# 1_Power.net
KiCad netlist of a schematic drawn in Altium Designer
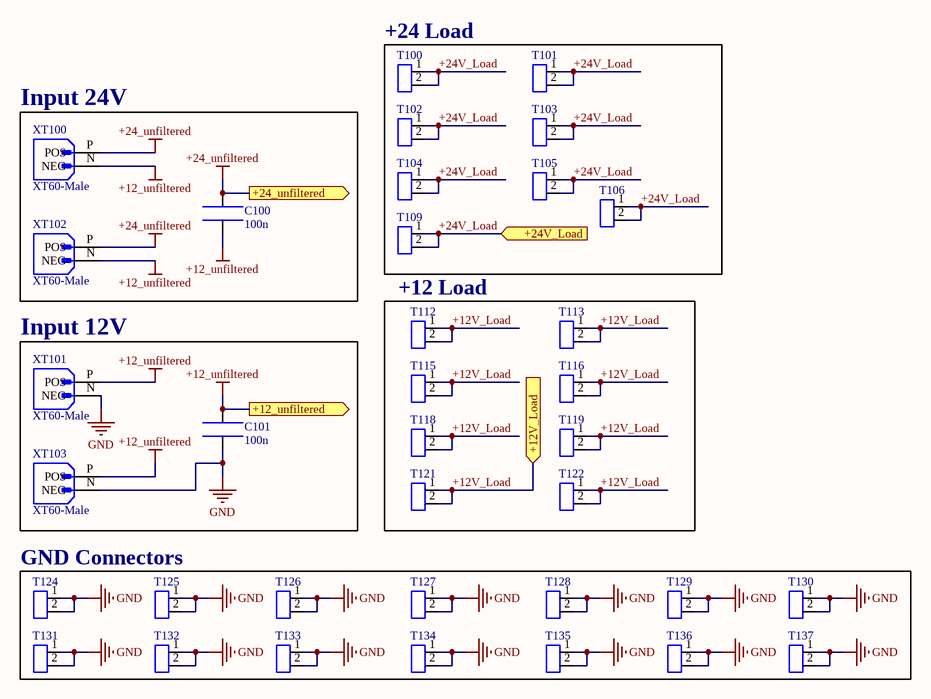
[diagram p0: 1_Power.SchDoc]

(export (version "E")
  (design (tool "Eeschema 10.0.6"))
  (components
    (comp (ref "C100") (value "100n") (footprint "C0805") (libsource (lib "MIA_LIBRARY") (part "C0805")))
    (comp (ref "C101") (value "100n") (footprint "C0805") (libsource (lib "MIA_LIBRARY") (part "C0805")))
    (comp (ref "T100")
      (value "Terminal pin 6.3mm")
      (footprint "Terminal pin 6.3mm")
      (libsource (lib "MIA_LIBRARY") (part "Terminal pin 6.3mm"))
    )
    (comp (ref "T101")
      (value "Terminal pin 6.3mm")
      (footprint "Terminal pin 6.3mm")
      (libsource (lib "MIA_LIBRARY") (part "Terminal pin 6.3mm"))
    )
    (comp (ref "T102")
      (value "Terminal pin 6.3mm")
      (footprint "Terminal pin 6.3mm")
      (libsource (lib "MIA_LIBRARY") (part "Terminal pin 6.3mm"))
    )
    (comp (ref "T103")
      (value "Terminal pin 6.3mm")
      (footprint "Terminal pin 6.3mm")
      (libsource (lib "MIA_LIBRARY") (part "Terminal pin 6.3mm"))
    )
    (comp (ref "T104")
      (value "Terminal pin 6.3mm")
      (footprint "Terminal pin 6.3mm")
      (libsource (lib "MIA_LIBRARY") (part "Terminal pin 6.3mm"))
    )
    (comp (ref "T105")
      (value "Terminal pin 6.3mm")
      (footprint "Terminal pin 6.3mm")
      (libsource (lib "MIA_LIBRARY") (part "Terminal pin 6.3mm"))
    )
    (comp (ref "T106")
      (value "Terminal pin 6.3mm")
      (footprint "Terminal pin 6.3mm")
      (libsource (lib "MIA_LIBRARY") (part "Terminal pin 6.3mm"))
    )
    (comp (ref "T109")
      (value "Terminal pin 6.3mm")
      (footprint "Terminal pin 6.3mm")
      (libsource (lib "MIA_LIBRARY") (part "Terminal pin 6.3mm"))
    )
    (comp (ref "T112")
      (value "Terminal pin 6.3mm")
      (footprint "Terminal pin 6.3mm")
      (libsource (lib "MIA_LIBRARY") (part "Terminal pin 6.3mm"))
    )
    (comp (ref "T113")
      (value "Terminal pin 6.3mm")
      (footprint "Terminal pin 6.3mm")
      (libsource (lib "MIA_LIBRARY") (part "Terminal pin 6.3mm"))
    )
    (comp (ref "T115")
      (value "Terminal pin 6.3mm")
      (footprint "Terminal pin 6.3mm")
      (libsource (lib "MIA_LIBRARY") (part "Terminal pin 6.3mm"))
    )
    (comp (ref "T116")
      (value "Terminal pin 6.3mm")
      (footprint "Terminal pin 6.3mm")
      (libsource (lib "MIA_LIBRARY") (part "Terminal pin 6.3mm"))
    )
    (comp (ref "T118")
      (value "Terminal pin 6.3mm")
      (footprint "Terminal pin 6.3mm")
      (libsource (lib "MIA_LIBRARY") (part "Terminal pin 6.3mm"))
    )
    (comp (ref "T119")
      (value "Terminal pin 6.3mm")
      (footprint "Terminal pin 6.3mm")
      (libsource (lib "MIA_LIBRARY") (part "Terminal pin 6.3mm"))
    )
    (comp (ref "T121")
      (value "Terminal pin 6.3mm")
      (footprint "Terminal pin 6.3mm")
      (libsource (lib "MIA_LIBRARY") (part "Terminal pin 6.3mm"))
    )
    (comp (ref "T122")
      (value "Terminal pin 6.3mm")
      (footprint "Terminal pin 6.3mm")
      (libsource (lib "MIA_LIBRARY") (part "Terminal pin 6.3mm"))
    )
    (comp (ref "T124")
      (value "Terminal pin 6.3mm")
      (footprint "Terminal pin 6.3mm")
      (libsource (lib "MIA_LIBRARY") (part "Terminal pin 6.3mm"))
    )
    (comp (ref "T125")
      (value "Terminal pin 6.3mm")
      (footprint "Terminal pin 6.3mm")
      (libsource (lib "MIA_LIBRARY") (part "Terminal pin 6.3mm"))
    )
    (comp (ref "T126")
      (value "Terminal pin 6.3mm")
      (footprint "Terminal pin 6.3mm")
      (libsource (lib "MIA_LIBRARY") (part "Terminal pin 6.3mm"))
    )
    (comp (ref "T127")
      (value "Terminal pin 6.3mm")
      (footprint "Terminal pin 6.3mm")
      (libsource (lib "MIA_LIBRARY") (part "Terminal pin 6.3mm"))
    )
    (comp (ref "T128")
      (value "Terminal pin 6.3mm")
      (footprint "Terminal pin 6.3mm")
      (libsource (lib "MIA_LIBRARY") (part "Terminal pin 6.3mm"))
    )
    (comp (ref "T129")
      (value "Terminal pin 6.3mm")
      (footprint "Terminal pin 6.3mm")
      (libsource (lib "MIA_LIBRARY") (part "Terminal pin 6.3mm"))
    )
    (comp (ref "T130")
      (value "Terminal pin 6.3mm")
      (footprint "Terminal pin 6.3mm")
      (libsource (lib "MIA_LIBRARY") (part "Terminal pin 6.3mm"))
    )
    (comp (ref "T131")
      (value "Terminal pin 6.3mm")
      (footprint "Terminal pin 6.3mm")
      (libsource (lib "MIA_LIBRARY") (part "Terminal pin 6.3mm"))
    )
    (comp (ref "T132")
      (value "Terminal pin 6.3mm")
      (footprint "Terminal pin 6.3mm")
      (libsource (lib "MIA_LIBRARY") (part "Terminal pin 6.3mm"))
    )
    (comp (ref "T133")
      (value "Terminal pin 6.3mm")
      (footprint "Terminal pin 6.3mm")
      (libsource (lib "MIA_LIBRARY") (part "Terminal pin 6.3mm"))
    )
    (comp (ref "T134")
      (value "Terminal pin 6.3mm")
      (footprint "Terminal pin 6.3mm")
      (libsource (lib "MIA_LIBRARY") (part "Terminal pin 6.3mm"))
    )
    (comp (ref "T135")
      (value "Terminal pin 6.3mm")
      (footprint "Terminal pin 6.3mm")
      (libsource (lib "MIA_LIBRARY") (part "Terminal pin 6.3mm"))
    )
    (comp (ref "T136")
      (value "Terminal pin 6.3mm")
      (footprint "Terminal pin 6.3mm")
      (libsource (lib "MIA_LIBRARY") (part "Terminal pin 6.3mm"))
    )
    (comp (ref "T137")
      (value "Terminal pin 6.3mm")
      (footprint "Terminal pin 6.3mm")
      (libsource (lib "MIA_LIBRARY") (part "Terminal pin 6.3mm"))
    )
    (comp (ref "XT100")
      (value "XT60-Male")
      (footprint "XT60-Male")
      (description "Plug; DC supply; XT60; male; PIN: 2; for cable; soldered; 30A; 500V")
      (fields (field (name "MP") "XT60-M") (field (name "MF") "AMASS"))
      (libsource (lib "MIA_LIBRARY") (part "XT60-Male"))
    )
    (comp (ref "XT101")
      (value "XT60-Male")
      (footprint "XT60-Male")
      (description "Plug; DC supply; XT60; male; PIN: 2; for cable; soldered; 30A; 500V")
      (fields (field (name "MP") "XT60-M") (field (name "MF") "AMASS"))
      (libsource (lib "MIA_LIBRARY") (part "XT60-Male"))
    )
    (comp (ref "XT102")
      (value "XT60-Male")
      (footprint "XT60-Male")
      (description "Plug; DC supply; XT60; male; PIN: 2; for cable; soldered; 30A; 500V")
      (fields (field (name "MP") "XT60-M") (field (name "MF") "AMASS"))
      (libsource (lib "MIA_LIBRARY") (part "XT60-Male"))
    )
    (comp (ref "XT103")
      (value "XT60-Male")
      (footprint "XT60-Male")
      (description "Plug; DC supply; XT60; male; PIN: 2; for cable; soldered; 30A; 500V")
      (fields (field (name "MP") "XT60-M") (field (name "MF") "AMASS"))
      (libsource (lib "MIA_LIBRARY") (part "XT60-Male"))
    )
  )
  (nets
    (net (code "1") (name "+12_unfiltered") (class "Default")
      (node (ref "C100") (pin "1") (pinfunction "1_1") (pintype "passive"))
      (node (ref "C101") (pin "1") (pinfunction "1_1") (pintype "passive"))
      (node (ref "XT100") (pin "N") (pinfunction "NEG_N") (pintype "passive"))
      (node (ref "XT101") (pin "P") (pinfunction "POS_P") (pintype "passive"))
      (node (ref "XT102") (pin "N") (pinfunction "NEG_N") (pintype "passive"))
      (node (ref "XT103") (pin "P") (pinfunction "POS_P") (pintype "passive"))
    )
    (net (code "2") (name "+24_unfiltered") (class "Default")
      (node (ref "C100") (pin "1") (pinfunction "1_1") (pintype "passive"))
      (node (ref "XT100") (pin "P") (pinfunction "POS_P") (pintype "passive"))
      (node (ref "XT102") (pin "P") (pinfunction "POS_P") (pintype "passive"))
    )
    (net (code "3") (name "/+12V_Load") (class "Default")
      (node (ref "T112") (pin "1") (pinfunction "1_1") (pintype "passive"))
      (node (ref "T112") (pin "2") (pinfunction "2_2") (pintype "passive"))
      (node (ref "T113") (pin "1") (pinfunction "1_1") (pintype "passive"))
      (node (ref "T113") (pin "2") (pinfunction "2_2") (pintype "passive"))
      (node (ref "T115") (pin "1") (pinfunction "1_1") (pintype "passive"))
      (node (ref "T115") (pin "2") (pinfunction "2_2") (pintype "passive"))
      (node (ref "T116") (pin "1") (pinfunction "1_1") (pintype "passive"))
      (node (ref "T116") (pin "2") (pinfunction "2_2") (pintype "passive"))
      (node (ref "T118") (pin "1") (pinfunction "1_1") (pintype "passive"))
      (node (ref "T118") (pin "2") (pinfunction "2_2") (pintype "passive"))
      (node (ref "T119") (pin "1") (pinfunction "1_1") (pintype "passive"))
      (node (ref "T119") (pin "2") (pinfunction "2_2") (pintype "passive"))
      (node (ref "T121") (pin "1") (pinfunction "1_1") (pintype "passive"))
      (node (ref "T121") (pin "2") (pinfunction "2_2") (pintype "passive"))
      (node (ref "T122") (pin "1") (pinfunction "1_1") (pintype "passive"))
      (node (ref "T122") (pin "2") (pinfunction "2_2") (pintype "passive"))
    )
    (net (code "4") (name "/+24V_Load") (class "Default")
      (node (ref "T100") (pin "1") (pinfunction "1_1") (pintype "passive"))
      (node (ref "T100") (pin "2") (pinfunction "2_2") (pintype "passive"))
      (node (ref "T101") (pin "1") (pinfunction "1_1") (pintype "passive"))
      (node (ref "T101") (pin "2") (pinfunction "2_2") (pintype "passive"))
      (node (ref "T102") (pin "1") (pinfunction "1_1") (pintype "passive"))
      (node (ref "T102") (pin "2") (pinfunction "2_2") (pintype "passive"))
      (node (ref "T103") (pin "1") (pinfunction "1_1") (pintype "passive"))
      (node (ref "T103") (pin "2") (pinfunction "2_2") (pintype "passive"))
      (node (ref "T104") (pin "1") (pinfunction "1_1") (pintype "passive"))
      (node (ref "T104") (pin "2") (pinfunction "2_2") (pintype "passive"))
      (node (ref "T105") (pin "1") (pinfunction "1_1") (pintype "passive"))
      (node (ref "T105") (pin "2") (pinfunction "2_2") (pintype "passive"))
      (node (ref "T106") (pin "1") (pinfunction "1_1") (pintype "passive"))
      (node (ref "T106") (pin "2") (pinfunction "2_2") (pintype "passive"))
      (node (ref "T109") (pin "1") (pinfunction "1_1") (pintype "passive"))
      (node (ref "T109") (pin "2") (pinfunction "2_2") (pintype "passive"))
    )
    (net (code "5") (name "GND") (class "Default")
      (node (ref "C101") (pin "1") (pinfunction "1_1") (pintype "passive"))
      (node (ref "T124") (pin "1") (pinfunction "1_1") (pintype "passive"))
      (node (ref "T124") (pin "2") (pinfunction "2_2") (pintype "passive"))
      (node (ref "T125") (pin "1") (pinfunction "1_1") (pintype "passive"))
      (node (ref "T125") (pin "2") (pinfunction "2_2") (pintype "passive"))
      (node (ref "T126") (pin "1") (pinfunction "1_1") (pintype "passive"))
      (node (ref "T126") (pin "2") (pinfunction "2_2") (pintype "passive"))
      (node (ref "T127") (pin "1") (pinfunction "1_1") (pintype "passive"))
      (node (ref "T127") (pin "2") (pinfunction "2_2") (pintype "passive"))
      (node (ref "T128") (pin "1") (pinfunction "1_1") (pintype "passive"))
      (node (ref "T128") (pin "2") (pinfunction "2_2") (pintype "passive"))
      (node (ref "T129") (pin "1") (pinfunction "1_1") (pintype "passive"))
      (node (ref "T129") (pin "2") (pinfunction "2_2") (pintype "passive"))
      (node (ref "T130") (pin "1") (pinfunction "1_1") (pintype "passive"))
      (node (ref "T130") (pin "2") (pinfunction "2_2") (pintype "passive"))
      (node (ref "T131") (pin "1") (pinfunction "1_1") (pintype "passive"))
      (node (ref "T131") (pin "2") (pinfunction "2_2") (pintype "passive"))
      (node (ref "T132") (pin "1") (pinfunction "1_1") (pintype "passive"))
      (node (ref "T132") (pin "2") (pinfunction "2_2") (pintype "passive"))
      (node (ref "T133") (pin "1") (pinfunction "1_1") (pintype "passive"))
      (node (ref "T133") (pin "2") (pinfunction "2_2") (pintype "passive"))
      (node (ref "T134") (pin "1") (pinfunction "1_1") (pintype "passive"))
      (node (ref "T134") (pin "2") (pinfunction "2_2") (pintype "passive"))
      (node (ref "T135") (pin "1") (pinfunction "1_1") (pintype "passive"))
      (node (ref "T135") (pin "2") (pinfunction "2_2") (pintype "passive"))
      (node (ref "T136") (pin "1") (pinfunction "1_1") (pintype "passive"))
      (node (ref "T136") (pin "2") (pinfunction "2_2") (pintype "passive"))
      (node (ref "T137") (pin "1") (pinfunction "1_1") (pintype "passive"))
      (node (ref "T137") (pin "2") (pinfunction "2_2") (pintype "passive"))
      (node (ref "XT101") (pin "N") (pinfunction "NEG_N") (pintype "passive"))
      (node (ref "XT103") (pin "N") (pinfunction "NEG_N") (pintype "passive"))
    )
  )
)
